# IDE_44m_to_40f.net
KiCad netlist of a schematic drawn in Altium Designer
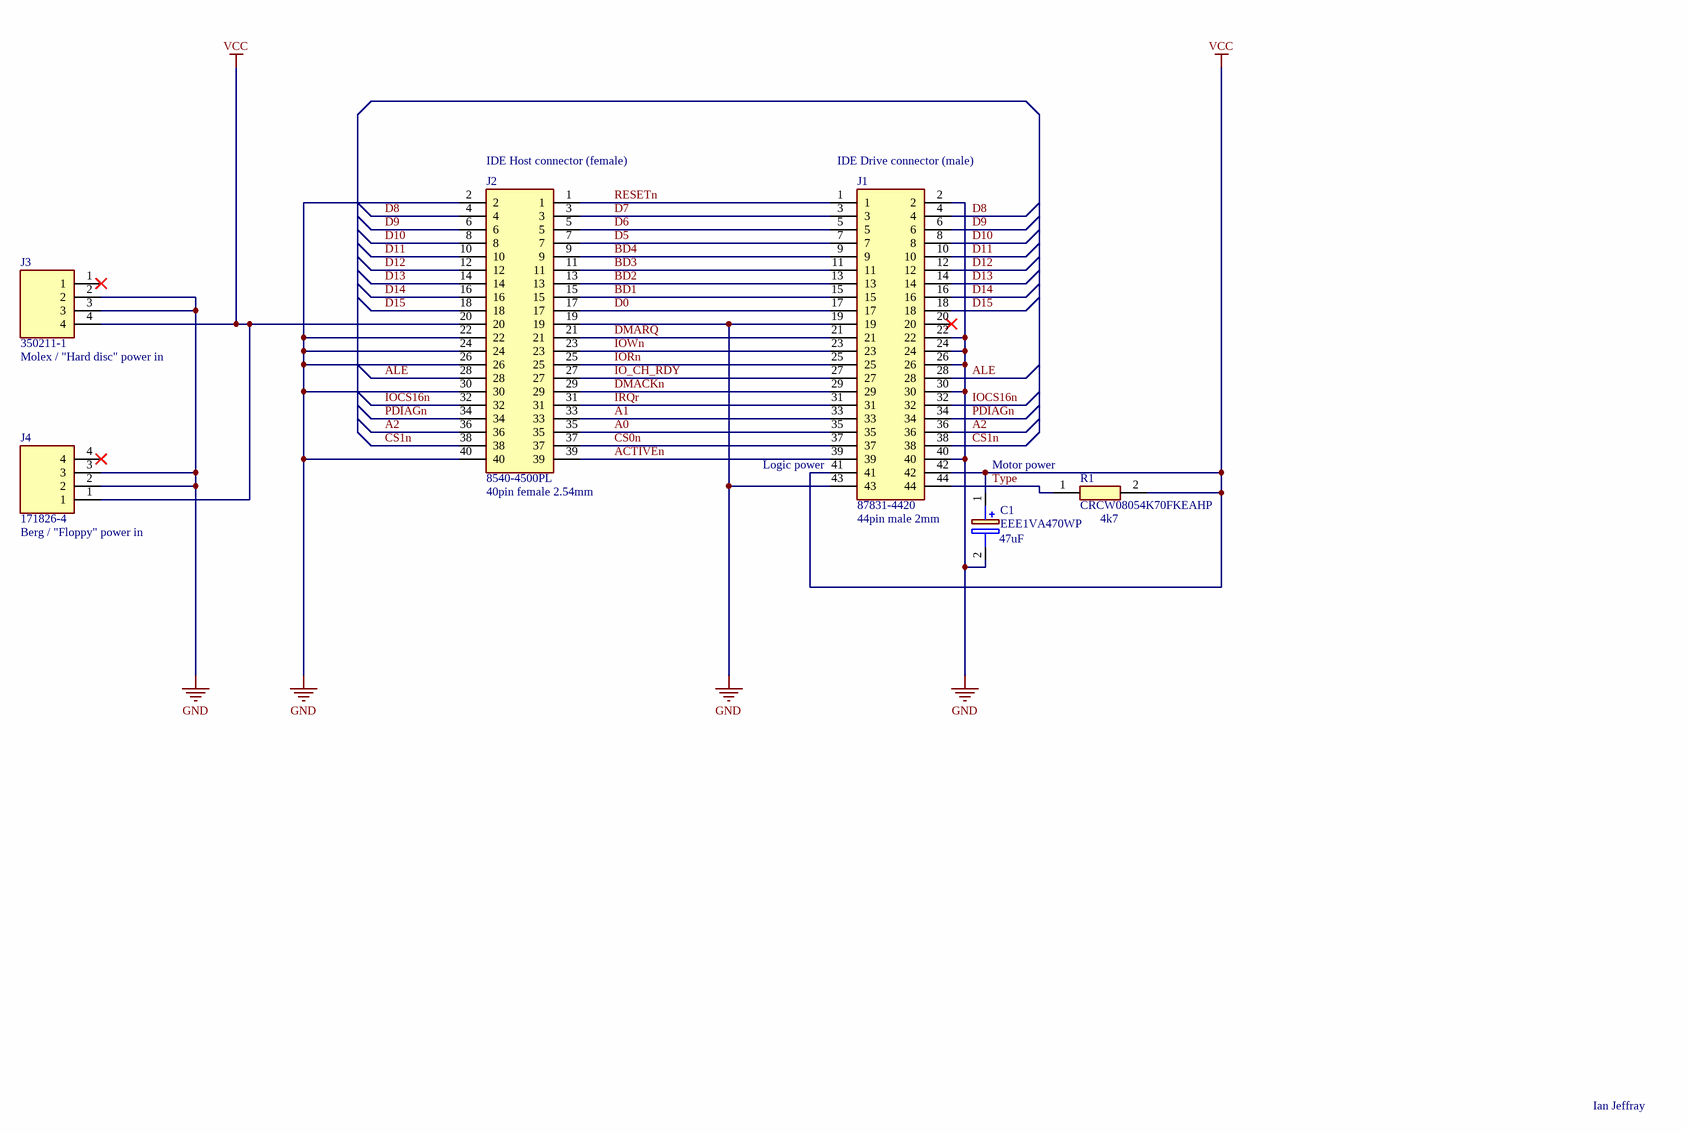
[diagram p0: IDE_44m_to_40f.SchDoc]

(export (version "E")
  (design (tool "Eeschema 10.0.6"))
  (components
    (comp (ref "C1")
      (value "EEE1VA470WP")
      (footprint "SamacSys:EEE1AA101SP")
      (description "Capacitor Polarised")
      (fields (field (name "ALTIUM_VALUE") "47uF"))
      (libsource (lib "*") (part "EEE1VA470WP"))
    )
    (comp (ref "J1")
      (value "87831-4420")
      (footprint "SamacSys:SHDR44W55P200_2X22_4665X630X640P")
      (description "Drive connector")
      (fields
        (field (name "MOUSER PART NUMBER") "538-87831-4420")
        (field (name "ALTIUM_VALUE") "44pin male 2mm")
      )
      (libsource (lib "*") (part "87831-4420"))
    )
    (comp (ref "J2")
      (value "8540-4500PL")
      (footprint "SamacSys:85404500PL")
      (description "Connector")
      (fields
        (field (name "MOUSER PART NUMBER") "517-8540-4500PL")
        (field (name "ALTIUM_VALUE") "40pin female 2.54mm")
      )
      (libsource (lib "*") (part "8540-4500PL"))
    )
    (comp (ref "J3")
      (value "350211-1")
      (footprint "SamacSys:3502111")
      (description "Alternate power input")
      (fields (field (name "MOUSER PART NUMBER") "571-3502111"))
      (libsource (lib "*") (part "350211-1"))
    )
    (comp (ref "J4")
      (value "171826-4")
      (footprint "SamacSys:SHDRRA4W69P0X250_1X4_1000X1350X670P")
      (description "Connector")
      (fields (field (name "MOUSER PART NUMBER") "571-1718264"))
      (libsource (lib "*") (part "171826-4"))
    )
    (comp (ref "R1")
      (value "CRCW08054K70FKEAHP")
      (footprint "SamacSys:RESC2012X50N")
      (description "4k7 Resistor")
      (fields (field (name "MOUSER PART NUMBER") "71-CRCW08054K70FKEAH") (field (name "ALTIUM_VALUE") "4k7"))
      (libsource (lib "*") (part "CRCW08054K70FKEAHP"))
    )
  )
  (nets
    (net (code "1") (name "/A0") (class "Default")
      (node (ref "J1") (pin "35") (pinfunction "35_35") (pintype "passive"))
      (node (ref "J2") (pin "35") (pinfunction "35_35") (pintype "passive"))
    )
    (net (code "2") (name "/A1") (class "Default")
      (node (ref "J1") (pin "33") (pinfunction "33_33") (pintype "passive"))
      (node (ref "J2") (pin "33") (pinfunction "33_33") (pintype "passive"))
    )
    (net (code "3") (name "/A2") (class "Default")
      (node (ref "J1") (pin "36") (pinfunction "36_36") (pintype "passive"))
      (node (ref "J2") (pin "36") (pinfunction "36_36") (pintype "passive"))
    )
    (net (code "4") (name "/ACTIVEn") (class "Default")
      (node (ref "J1") (pin "39") (pinfunction "39_39") (pintype "passive"))
      (node (ref "J2") (pin "39") (pinfunction "39_39") (pintype "passive"))
    )
    (net (code "5") (name "/ALE") (class "Default")
      (node (ref "J1") (pin "28") (pinfunction "28_28") (pintype "passive"))
      (node (ref "J2") (pin "28") (pinfunction "28_28") (pintype "passive"))
    )
    (net (code "6") (name "/BD1") (class "Default")
      (node (ref "J1") (pin "15") (pinfunction "15_15") (pintype "passive"))
      (node (ref "J2") (pin "15") (pinfunction "15_15") (pintype "passive"))
    )
    (net (code "7") (name "/BD2") (class "Default")
      (node (ref "J1") (pin "13") (pinfunction "13_13") (pintype "passive"))
      (node (ref "J2") (pin "13") (pinfunction "13_13") (pintype "passive"))
    )
    (net (code "8") (name "/BD3") (class "Default")
      (node (ref "J1") (pin "11") (pinfunction "11_11") (pintype "passive"))
      (node (ref "J2") (pin "11") (pinfunction "11_11") (pintype "passive"))
    )
    (net (code "9") (name "/BD4") (class "Default")
      (node (ref "J1") (pin "9") (pinfunction "9_9") (pintype "passive"))
      (node (ref "J2") (pin "9") (pinfunction "9_9") (pintype "passive"))
    )
    (net (code "10") (name "/CS0n") (class "Default")
      (node (ref "J1") (pin "37") (pinfunction "37_37") (pintype "passive"))
      (node (ref "J2") (pin "37") (pinfunction "37_37") (pintype "passive"))
    )
    (net (code "11") (name "/CS1n") (class "Default")
      (node (ref "J1") (pin "38") (pinfunction "38_38") (pintype "passive"))
      (node (ref "J2") (pin "38") (pinfunction "38_38") (pintype "passive"))
    )
    (net (code "12") (name "/D0") (class "Default")
      (node (ref "J1") (pin "17") (pinfunction "17_17") (pintype "passive"))
      (node (ref "J2") (pin "17") (pinfunction "17_17") (pintype "passive"))
    )
    (net (code "13") (name "/D5") (class "Default")
      (node (ref "J1") (pin "7") (pinfunction "7_7") (pintype "passive"))
      (node (ref "J2") (pin "7") (pinfunction "7_7") (pintype "passive"))
    )
    (net (code "14") (name "/D6") (class "Default")
      (node (ref "J1") (pin "5") (pinfunction "5_5") (pintype "passive"))
      (node (ref "J2") (pin "5") (pinfunction "5_5") (pintype "passive"))
    )
    (net (code "15") (name "/D7") (class "Default")
      (node (ref "J1") (pin "3") (pinfunction "3_3") (pintype "passive"))
      (node (ref "J2") (pin "3") (pinfunction "3_3") (pintype "passive"))
    )
    (net (code "16") (name "/D8") (class "Default")
      (node (ref "J1") (pin "4") (pinfunction "4_4") (pintype "passive"))
      (node (ref "J2") (pin "4") (pinfunction "4_4") (pintype "passive"))
    )
    (net (code "17") (name "/D9") (class "Default")
      (node (ref "J1") (pin "6") (pinfunction "6_6") (pintype "passive"))
      (node (ref "J2") (pin "6") (pinfunction "6_6") (pintype "passive"))
    )
    (net (code "18") (name "/D10") (class "Default")
      (node (ref "J1") (pin "8") (pinfunction "8_8") (pintype "passive"))
      (node (ref "J2") (pin "8") (pinfunction "8_8") (pintype "passive"))
    )
    (net (code "19") (name "/D11") (class "Default")
      (node (ref "J1") (pin "10") (pinfunction "10_10") (pintype "passive"))
      (node (ref "J2") (pin "10") (pinfunction "10_10") (pintype "passive"))
    )
    (net (code "20") (name "/D12") (class "Default")
      (node (ref "J1") (pin "12") (pinfunction "12_12") (pintype "passive"))
      (node (ref "J2") (pin "12") (pinfunction "12_12") (pintype "passive"))
    )
    (net (code "21") (name "/D13") (class "Default")
      (node (ref "J1") (pin "14") (pinfunction "14_14") (pintype "passive"))
      (node (ref "J2") (pin "14") (pinfunction "14_14") (pintype "passive"))
    )
    (net (code "22") (name "/D14") (class "Default")
      (node (ref "J1") (pin "16") (pinfunction "16_16") (pintype "passive"))
      (node (ref "J2") (pin "16") (pinfunction "16_16") (pintype "passive"))
    )
    (net (code "23") (name "/D15") (class "Default")
      (node (ref "J1") (pin "18") (pinfunction "18_18") (pintype "passive"))
      (node (ref "J2") (pin "18") (pinfunction "18_18") (pintype "passive"))
    )
    (net (code "24") (name "/DMACKn") (class "Default")
      (node (ref "J1") (pin "29") (pinfunction "29_29") (pintype "passive"))
      (node (ref "J2") (pin "29") (pinfunction "29_29") (pintype "passive"))
    )
    (net (code "25") (name "/DMARQ") (class "Default")
      (node (ref "J1") (pin "21") (pinfunction "21_21") (pintype "passive"))
      (node (ref "J2") (pin "21") (pinfunction "21_21") (pintype "passive"))
    )
    (net (code "26") (name "/IOCS16n") (class "Default")
      (node (ref "J1") (pin "32") (pinfunction "32_32") (pintype "passive"))
      (node (ref "J2") (pin "32") (pinfunction "32_32") (pintype "passive"))
    )
    (net (code "27") (name "/IORn") (class "Default")
      (node (ref "J1") (pin "25") (pinfunction "25_25") (pintype "passive"))
      (node (ref "J2") (pin "25") (pinfunction "25_25") (pintype "passive"))
    )
    (net (code "28") (name "/IOWn") (class "Default")
      (node (ref "J1") (pin "23") (pinfunction "23_23") (pintype "passive"))
      (node (ref "J2") (pin "23") (pinfunction "23_23") (pintype "passive"))
    )
    (net (code "29") (name "/IO_CH_RDY") (class "Default")
      (node (ref "J1") (pin "27") (pinfunction "27_27") (pintype "passive"))
      (node (ref "J2") (pin "27") (pinfunction "27_27") (pintype "passive"))
    )
    (net (code "30") (name "/IRQr") (class "Default")
      (node (ref "J1") (pin "31") (pinfunction "31_31") (pintype "passive"))
      (node (ref "J2") (pin "31") (pinfunction "31_31") (pintype "passive"))
    )
    (net (code "31") (name "/PDIAGn") (class "Default")
      (node (ref "J1") (pin "34") (pinfunction "34_34") (pintype "passive"))
      (node (ref "J2") (pin "34") (pinfunction "34_34") (pintype "passive"))
    )
    (net (code "32") (name "/RESETn") (class "Default")
      (node (ref "J1") (pin "1") (pinfunction "1_1") (pintype "passive"))
      (node (ref "J2") (pin "1") (pinfunction "1_1") (pintype "passive"))
    )
    (net (code "33") (name "/Type") (class "Default")
      (node (ref "J1") (pin "44") (pinfunction "44_44") (pintype "passive"))
      (node (ref "R1") (pin "1") (pinfunction "1_1") (pintype "passive"))
    )
    (net (code "34") (name "GND") (class "Default")
      (node (ref "C1") (pin "2") (pinfunction "-_2") (pintype "passive"))
      (node (ref "J1") (pin "19") (pinfunction "19_19") (pintype "passive"))
      (node (ref "J1") (pin "2") (pinfunction "2_2") (pintype "passive"))
      (node (ref "J1") (pin "22") (pinfunction "22_22") (pintype "passive"))
      (node (ref "J1") (pin "24") (pinfunction "24_24") (pintype "passive"))
      (node (ref "J1") (pin "26") (pinfunction "26_26") (pintype "passive"))
      (node (ref "J1") (pin "30") (pinfunction "30_30") (pintype "passive"))
      (node (ref "J1") (pin "40") (pinfunction "40_40") (pintype "passive"))
      (node (ref "J1") (pin "43") (pinfunction "43_43") (pintype "passive"))
      (node (ref "J2") (pin "19") (pinfunction "19_19") (pintype "passive"))
      (node (ref "J2") (pin "2") (pinfunction "2_2") (pintype "passive"))
      (node (ref "J2") (pin "22") (pinfunction "22_22") (pintype "passive"))
      (node (ref "J2") (pin "24") (pinfunction "24_24") (pintype "passive"))
      (node (ref "J2") (pin "26") (pinfunction "26_26") (pintype "passive"))
      (node (ref "J2") (pin "30") (pinfunction "30_30") (pintype "passive"))
      (node (ref "J2") (pin "40") (pinfunction "40_40") (pintype "passive"))
      (node (ref "J3") (pin "2") (pinfunction "2_2") (pintype "passive"))
      (node (ref "J3") (pin "3") (pinfunction "3_3") (pintype "passive"))
      (node (ref "J4") (pin "2") (pinfunction "2_2") (pintype "passive"))
      (node (ref "J4") (pin "3") (pinfunction "3_3") (pintype "passive"))
    )
    (net (code "35") (name "VCC") (class "Default")
      (node (ref "C1") (pin "1") (pinfunction "+_1") (pintype "passive"))
      (node (ref "J1") (pin "41") (pinfunction "41_41") (pintype "passive"))
      (node (ref "J1") (pin "42") (pinfunction "42_42") (pintype "passive"))
      (node (ref "J2") (pin "20") (pinfunction "20_20") (pintype "passive"))
      (node (ref "J3") (pin "4") (pinfunction "4_4") (pintype "passive"))
      (node (ref "J4") (pin "1") (pinfunction "1_1") (pintype "passive"))
      (node (ref "R1") (pin "2") (pinfunction "2_2") (pintype "passive"))
    )
    (net (code "36") (name "unconnected-(J1-Pad20)") (class "Default")
      (node (ref "J1") (pin "20") (pinfunction "20_20") (pintype "passive+no_connect"))
    )
    (net (code "37") (name "unconnected-(J3-Pad1)") (class "Default")
      (node (ref "J3") (pin "1") (pinfunction "1_1") (pintype "passive+no_connect"))
    )
    (net (code "38") (name "unconnected-(J4-Pad4)") (class "Default")
      (node (ref "J4") (pin "4") (pinfunction "4_4") (pintype "passive+no_connect"))
    )
  )
)
